# usb.net
KiCad netlist of a schematic drawn in Altium Designer
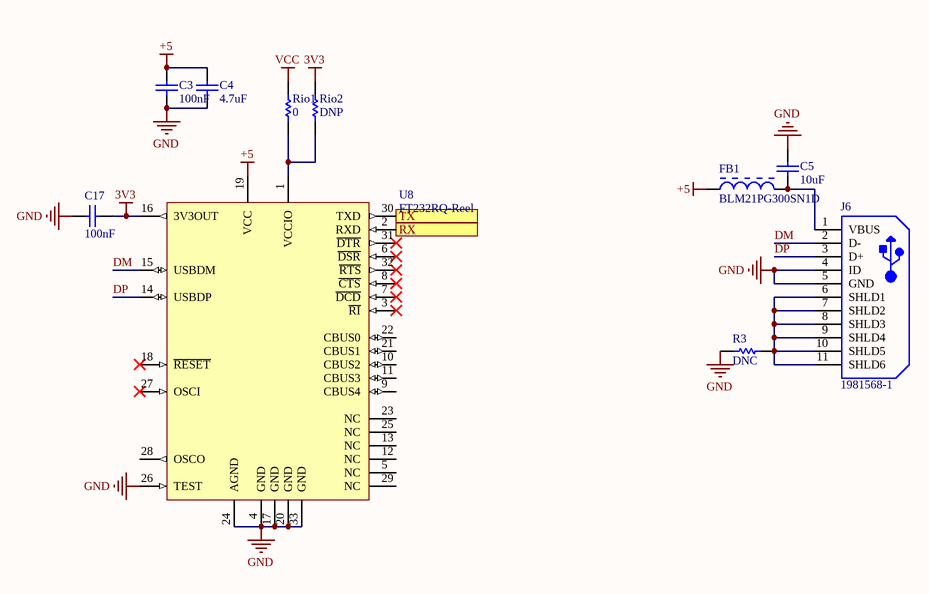
[diagram p0: usb.SchDoc]

(export (version "E")
  (design (tool "Eeschema 10.0.6"))
  (components
    (comp (ref "C3")
      (value "100nF")
      (footprint "0402")
      (description "Ceramic Capacitor (Surface Mount)")
      (fields (field (name "MANUFACTURER") "Generic Ceramic Chip Cap (TBD)") (field (name "Comment") "Cap"))
      (libsource (lib "nextgaze") (part "Cap"))
    )
    (comp (ref "C4")
      (value "4.7uF")
      (footprint "0402")
      (description "Ceramic Capacitor (Surface Mount)")
      (fields (field (name "MANUFACTURER") "Generic Ceramic Chip Cap (TBD)") (field (name "Comment") "Cap"))
      (libsource (lib "nextgaze") (part "Cap"))
    )
    (comp (ref "C5")
      (value "10uF")
      (footprint "0402")
      (description "Ceramic Capacitor (Surface Mount)")
      (fields (field (name "MANUFACTURER") "Generic Ceramic Chip Cap (TBD)") (field (name "Comment") "Cap"))
      (libsource (lib "nextgaze") (part "Cap"))
    )
    (comp (ref "C17")
      (value "100nF")
      (footprint "0402")
      (description "Ceramic Capacitor (Surface Mount)")
      (fields (field (name "MANUFACTURER") "Generic Ceramic Chip Cap (TBD)") (field (name "Comment") "Cap"))
      (libsource (lib "nextgaze") (part "Cap"))
    )
    (comp (ref "FB1")
      (value "BLM21PG300SN1D")
      (footprint "MURA-BLM21-B40-CHIP-2_V2")
      (fields (field (name "MANUFACTURER") "Murata"))
      (libsource (lib "Altium Content Vault") (part "MURA-FB-2"))
    )
    (comp (ref "J6")
      (value "1981568-1")
      (footprint "TECO-1981568-5_V")
      (description "Micro USB Receptacle Standard Type B Assy, 5-Pin SMD, RoHS, Tape and Reel")
      (fields (field (name "MANUFACTURER") "TE Connectivity"))
      (libsource (lib "Altium Content Vault") (part "USB-5-6SHLD"))
    )
    (comp (ref "R3")
      (value "DNC")
      (footprint "0402")
      (description "Chip Resistor (Surface Mount)")
      (fields (field (name "MANUFACTURER") "Generic Chip Res (TBD)") (field (name "Comment") "Res"))
      (libsource (lib "maglib") (part "Res"))
    )
    (comp (ref "Rio1")
      (value "0")
      (footprint "0402")
      (description "Chip Resistor (Surface Mount)")
      (fields (field (name "MANUFACTURER") "Generic Chip Res (TBD)") (field (name "Comment") "Res"))
      (libsource (lib "maglib") (part "Res"))
    )
    (comp (ref "Rio2")
      (value "DNP")
      (footprint "0402")
      (description "Chip Resistor (Surface Mount)")
      (fields (field (name "MANUFACTURER") "Generic Chip Res (TBD)") (field (name "Comment") "Res"))
      (libsource (lib "maglib") (part "Res"))
    )
    (comp (ref "U8")
      (value "FT232RQ-Reel")
      (footprint "PQFN5X5-32_V")
      (description "USB UART Asynchronous Serial Data Transfer Chip, 32-pin QFN, Tape and Reel")
      (fields (field (name "MANUFACTURER") "FTDI"))
      (libsource (lib "Altium Content Vault") (part "COM-UART-FT232R-SQ32"))
    )
  )
  (nets
    (net (code "1") (name "+5") (class "Default")
      (node (ref "C3") (pin "2") (pinfunction "2_2") (pintype "passive"))
      (node (ref "C4") (pin "2") (pinfunction "2_2") (pintype "passive"))
      (node (ref "FB1") (pin "1") (pinfunction "1_1") (pintype "passive"))
      (node (ref "U8") (pin "19") (pinfunction "VCC_19") (pintype "power_in"))
    )
    (net (code "2") (name "/DM") (class "Default")
      (node (ref "J6") (pin "2") (pinfunction "D-_2") (pintype "passive"))
      (node (ref "U8") (pin "15") (pinfunction "USBDM_15") (pintype "bidirectional"))
    )
    (net (code "3") (name "/DP") (class "Default")
      (node (ref "J6") (pin "3") (pinfunction "D+_3") (pintype "passive"))
      (node (ref "U8") (pin "14") (pinfunction "USBDP_14") (pintype "bidirectional"))
    )
    (net (code "4") (name "/RX") (class "Default")
      (node (ref "U8") (pin "2") (pinfunction "RXD_2") (pintype "input"))
    )
    (net (code "5") (name "/TX") (class "Default")
      (node (ref "U8") (pin "30") (pinfunction "TXD_30") (pintype "output"))
    )
    (net (code "6") (name "3V3") (class "Default")
      (node (ref "C17") (pin "2") (pinfunction "2_2") (pintype "passive"))
      (node (ref "Rio2") (pin "2") (pinfunction "2_2") (pintype "passive"))
      (node (ref "U8") (pin "16") (pinfunction "3V3OUT_16") (pintype "output"))
    )
    (net (code "7") (name "GND") (class "Default")
      (node (ref "C17") (pin "1") (pinfunction "1_1") (pintype "passive"))
      (node (ref "C3") (pin "1") (pinfunction "1_1") (pintype "passive"))
      (node (ref "C4") (pin "1") (pinfunction "1_1") (pintype "passive"))
      (node (ref "C5") (pin "2") (pinfunction "2_2") (pintype "passive"))
      (node (ref "J6") (pin "4") (pinfunction "ID_4") (pintype "passive"))
      (node (ref "J6") (pin "5") (pinfunction "GND_5") (pintype "passive"))
      (node (ref "R3") (pin "1") (pinfunction "1_1") (pintype "passive"))
      (node (ref "U8") (pin "17") (pinfunction "GND_17") (pintype "power_in"))
      (node (ref "U8") (pin "20") (pinfunction "GND_20") (pintype "power_in"))
      (node (ref "U8") (pin "24") (pinfunction "AGND_24") (pintype "power_in"))
      (node (ref "U8") (pin "26") (pinfunction "TEST_26") (pintype "input"))
      (node (ref "U8") (pin "33") (pinfunction "GND_33") (pintype "power_in"))
      (node (ref "U8") (pin "4") (pinfunction "GND_4") (pintype "power_in"))
    )
    (net (code "8") (name "Net-(J6-SHLD1)") (class "Default")
      (node (ref "J6") (pin "10") (pinfunction "SHLD5_10") (pintype "passive"))
      (node (ref "J6") (pin "11") (pinfunction "SHLD6_11") (pintype "passive"))
      (node (ref "J6") (pin "6") (pinfunction "SHLD1_6") (pintype "passive"))
      (node (ref "J6") (pin "7") (pinfunction "SHLD2_7") (pintype "passive"))
      (node (ref "J6") (pin "8") (pinfunction "SHLD3_8") (pintype "passive"))
      (node (ref "J6") (pin "9") (pinfunction "SHLD4_9") (pintype "passive"))
      (node (ref "R3") (pin "2") (pinfunction "2_2") (pintype "passive"))
    )
    (net (code "9") (name "Net-(J6-VBUS)") (class "Default")
      (node (ref "C5") (pin "1") (pinfunction "1_1") (pintype "passive"))
      (node (ref "FB1") (pin "2") (pinfunction "2_2") (pintype "passive"))
      (node (ref "J6") (pin "1") (pinfunction "VBUS_1") (pintype "passive"))
    )
    (net (code "10") (name "Net-(U8-VCCIO)") (class "Default")
      (node (ref "Rio1") (pin "1") (pinfunction "1_1") (pintype "passive"))
      (node (ref "Rio2") (pin "1") (pinfunction "1_1") (pintype "passive"))
      (node (ref "U8") (pin "1") (pinfunction "VCCIO_1") (pintype "power_in"))
    )
    (net (code "11") (name "VCC") (class "Default")
      (node (ref "Rio1") (pin "2") (pinfunction "2_2") (pintype "passive"))
    )
    (net (code "12") (name "unconnected-(U8-CBUS0-Pad22)") (class "Default")
      (node (ref "U8") (pin "22") (pinfunction "CBUS0_22") (pintype "bidirectional"))
    )
    (net (code "13") (name "unconnected-(U8-CBUS1-Pad21)") (class "Default")
      (node (ref "U8") (pin "21") (pinfunction "CBUS1_21") (pintype "bidirectional"))
    )
    (net (code "14") (name "unconnected-(U8-CBUS2-Pad10)") (class "Default")
      (node (ref "U8") (pin "10") (pinfunction "CBUS2_10") (pintype "bidirectional"))
    )
    (net (code "15") (name "unconnected-(U8-CBUS3-Pad11)") (class "Default")
      (node (ref "U8") (pin "11") (pinfunction "CBUS3_11") (pintype "bidirectional"))
    )
    (net (code "16") (name "unconnected-(U8-CBUS4-Pad9)") (class "Default")
      (node (ref "U8") (pin "9") (pinfunction "CBUS4_9") (pintype "bidirectional"))
    )
    (net (code "17") (name "unconnected-(U8-NC-Pad5)") (class "Default")
      (node (ref "U8") (pin "5") (pinfunction "NC_5") (pintype "passive"))
    )
    (net (code "18") (name "unconnected-(U8-NC-Pad12)") (class "Default")
      (node (ref "U8") (pin "12") (pinfunction "NC_12") (pintype "passive"))
    )
    (net (code "19") (name "unconnected-(U8-NC-Pad13)") (class "Default")
      (node (ref "U8") (pin "13") (pinfunction "NC_13") (pintype "passive"))
    )
    (net (code "20") (name "unconnected-(U8-NC-Pad23)") (class "Default")
      (node (ref "U8") (pin "23") (pinfunction "NC_23") (pintype "passive"))
    )
    (net (code "21") (name "unconnected-(U8-NC-Pad25)") (class "Default")
      (node (ref "U8") (pin "25") (pinfunction "NC_25") (pintype "passive"))
    )
    (net (code "22") (name "unconnected-(U8-NC-Pad29)") (class "Default")
      (node (ref "U8") (pin "29") (pinfunction "NC_29") (pintype "passive"))
    )
    (net (code "23") (name "unconnected-(U8-OSCI-Pad27)") (class "Default")
      (node (ref "U8") (pin "27") (pinfunction "OSCI_27") (pintype "input+no_connect"))
    )
    (net (code "24") (name "unconnected-(U8-OSCO-Pad28)") (class "Default")
      (node (ref "U8") (pin "28") (pinfunction "OSCO_28") (pintype "output"))
    )
    (net (code "25") (name "unconnected-(U8-~{CTS}-Pad8)") (class "Default")
      (node (ref "U8") (pin "8") (pinfunction "~{CTS}_8") (pintype "input+no_connect"))
    )
    (net (code "26") (name "unconnected-(U8-~{DCD}-Pad7)") (class "Default")
      (node (ref "U8") (pin "7") (pinfunction "~{DCD}_7") (pintype "input+no_connect"))
    )
    (net (code "27") (name "unconnected-(U8-~{DSR}-Pad6)") (class "Default")
      (node (ref "U8") (pin "6") (pinfunction "~{DSR}_6") (pintype "input+no_connect"))
    )
    (net (code "28") (name "unconnected-(U8-~{DTR}-Pad31)") (class "Default")
      (node (ref "U8") (pin "31") (pinfunction "~{DTR}_31") (pintype "output+no_connect"))
    )
    (net (code "29") (name "unconnected-(U8-~{RESET}-Pad18)") (class "Default")
      (node (ref "U8") (pin "18") (pinfunction "~{RESET}_18") (pintype "input+no_connect"))
    )
    (net (code "30") (name "unconnected-(U8-~{RI}-Pad3)") (class "Default")
      (node (ref "U8") (pin "3") (pinfunction "~{RI}_3") (pintype "input+no_connect"))
    )
    (net (code "31") (name "unconnected-(U8-~{RTS}-Pad32)") (class "Default")
      (node (ref "U8") (pin "32") (pinfunction "~{RTS}_32") (pintype "output+no_connect"))
    )
  )
)
